# LMP9100_breakout_V2.net
KiCad netlist of a schematic drawn in EAGLE
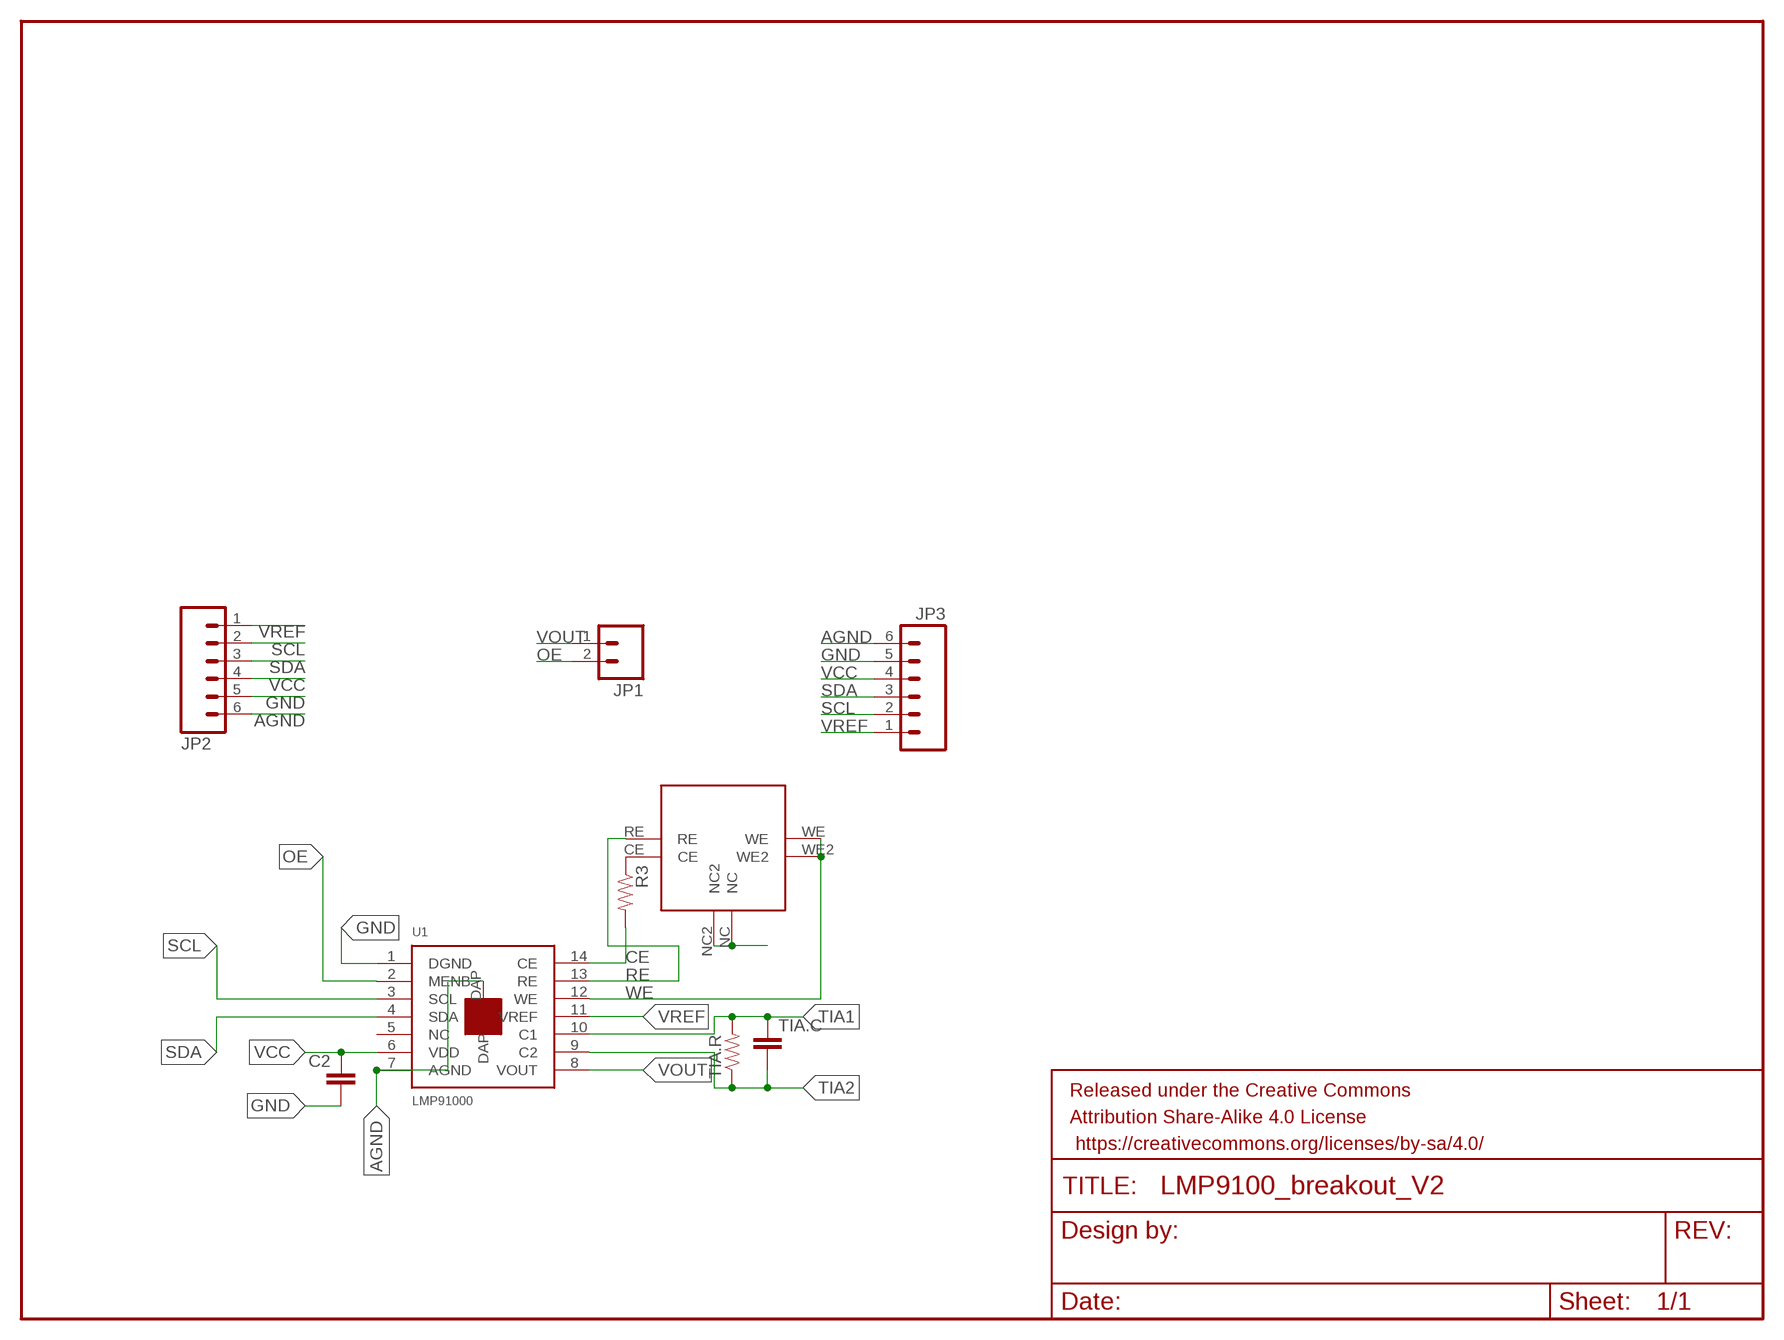
[diagram p0: schematic, sheet 1]

(export (version "E")
  (design (tool "Eeschema 10.0.6"))
  (components
    (comp (ref "C2")
      (value "CAP0603-CAP")
      (footprint "eagle-import:0603-CAP")
      (libsource (lib "eagle-import") (part "CAP0603-CAP"))
    )
    (comp (ref "FRAME1")
      (value "FRAME-LETTER")
      (footprint "eagle-import:CREATIVE_COMMONS")
      (libsource (lib "eagle-import") (part "FRAME-LETTER"))
    )
    (comp (ref "JP1")
      (value "M02PTH")
      (footprint "eagle-import:1X02")
      (libsource (lib "eagle-import") (part "M02PTH"))
    )
    (comp (ref "JP2")
      (value "M06SILK_FEMALE_PTH")
      (footprint "eagle-import:1X06")
      (libsource (lib "eagle-import") (part "M06SILK_FEMALE_PTH"))
    )
    (comp (ref "JP3")
      (value "M06SILK_FEMALE_PTH")
      (footprint "eagle-import:1X06")
      (libsource (lib "eagle-import") (part "M06SILK_FEMALE_PTH"))
    )
    (comp (ref "R3")
      (value "RESISTOR0603-RES")
      (footprint "eagle-import:0603-RES")
      (libsource (lib "eagle-import") (part "RESISTOR0603-RES"))
    )
    (comp (ref "TIA.C")
      (value "CAP0603-CAP")
      (footprint "eagle-import:0603-CAP")
      (libsource (lib "eagle-import") (part "CAP0603-CAP"))
    )
    (comp (ref "TIA.R")
      (value "RESISTOR0603-RES")
      (footprint "eagle-import:0603-RES")
      (libsource (lib "eagle-import") (part "RESISTOR0603-RES"))
    )
    (comp (ref "U$1")
      (value "SPEC-SENSOR")
      (footprint "eagle-import:SPEC-SENSOR")
      (libsource (lib "eagle-import") (part "SPEC-SENSOR"))
    )
    (comp (ref "U1")
      (value "LMP91000")
      (footprint "eagle-import:LMP91000")
      (libsource (lib "eagle-import") (part "LMP91000"))
    )
  )
  (nets
    (net (code "1") (name "/CE") (class "Default")
      (node (ref "R3") (pin "2") (pinfunction "2_2") (pintype "passive"))
      (node (ref "U1") (pin "14") (pinfunction "CE_14") (pintype "bidirectional"))
    )
    (net (code "2") (name "/RE") (class "Default")
      (node (ref "U$1") (pin "RE") (pinfunction "RE_RE") (pintype "bidirectional"))
      (node (ref "U1") (pin "13") (pinfunction "RE_13") (pintype "bidirectional"))
    )
    (net (code "3") (name "/WE") (class "Default")
      (node (ref "U$1") (pin "WE") (pinfunction "WE_WE") (pintype "bidirectional"))
      (node (ref "U$1") (pin "WE2") (pinfunction "WE2_WE2") (pintype "bidirectional"))
      (node (ref "U1") (pin "12") (pinfunction "WE_12") (pintype "bidirectional"))
    )
    (net (code "4") (name "AGND") (class "Default")
      (node (ref "JP2") (pin "6") (pinfunction "6_6") (pintype "passive"))
      (node (ref "JP3") (pin "6") (pinfunction "6_6") (pintype "passive"))
      (node (ref "U1") (pin "7") (pinfunction "AGND_7") (pintype "bidirectional"))
      (node (ref "U1") (pin "DAP") (pinfunction "DAP_DAP") (pintype "bidirectional"))
    )
    (net (code "5") (name "GND") (class "Default")
      (node (ref "C2") (pin "2") (pinfunction "2_2") (pintype "passive"))
      (node (ref "JP2") (pin "5") (pinfunction "5_5") (pintype "passive"))
      (node (ref "JP3") (pin "5") (pinfunction "5_5") (pintype "passive"))
      (node (ref "U$1") (pin "NC") (pinfunction "NC_NC") (pintype "bidirectional"))
      (node (ref "U$1") (pin "NC2") (pinfunction "NC2_NC2") (pintype "bidirectional"))
      (node (ref "U1") (pin "1") (pinfunction "DGND_1") (pintype "bidirectional"))
    )
    (net (code "6") (name "Net-(R3-Pad1)") (class "Default")
      (node (ref "R3") (pin "1") (pinfunction "1_1") (pintype "passive"))
      (node (ref "U$1") (pin "CE") (pinfunction "CE_CE") (pintype "bidirectional"))
    )
    (net (code "7") (name "OE") (class "Default")
      (node (ref "JP1") (pin "2") (pinfunction "2_2") (pintype "passive"))
      (node (ref "U1") (pin "2") (pinfunction "MENB_2") (pintype "bidirectional"))
    )
    (net (code "8") (name "SCL") (class "Default")
      (node (ref "JP2") (pin "2") (pinfunction "2_2") (pintype "passive"))
      (node (ref "JP3") (pin "2") (pinfunction "2_2") (pintype "passive"))
      (node (ref "U1") (pin "3") (pinfunction "SCL_3") (pintype "bidirectional"))
    )
    (net (code "9") (name "SDA") (class "Default")
      (node (ref "JP2") (pin "3") (pinfunction "3_3") (pintype "passive"))
      (node (ref "JP3") (pin "3") (pinfunction "3_3") (pintype "passive"))
      (node (ref "U1") (pin "4") (pinfunction "SDA_4") (pintype "bidirectional"))
    )
    (net (code "10") (name "TIA1") (class "Default")
      (node (ref "TIA.C") (pin "1") (pinfunction "1_1") (pintype "passive"))
      (node (ref "TIA.R") (pin "2") (pinfunction "2_2") (pintype "passive"))
      (node (ref "U1") (pin "10") (pinfunction "C1_10") (pintype "bidirectional"))
    )
    (net (code "11") (name "TIA2") (class "Default")
      (node (ref "TIA.C") (pin "2") (pinfunction "2_2") (pintype "passive"))
      (node (ref "TIA.R") (pin "1") (pinfunction "1_1") (pintype "passive"))
      (node (ref "U1") (pin "9") (pinfunction "C2_9") (pintype "bidirectional"))
    )
    (net (code "12") (name "VCC") (class "Default")
      (node (ref "C2") (pin "1") (pinfunction "1_1") (pintype "passive"))
      (node (ref "JP2") (pin "4") (pinfunction "4_4") (pintype "passive"))
      (node (ref "JP3") (pin "4") (pinfunction "4_4") (pintype "passive"))
      (node (ref "U1") (pin "6") (pinfunction "VDD_6") (pintype "bidirectional"))
    )
    (net (code "13") (name "VOUT") (class "Default")
      (node (ref "JP1") (pin "1") (pinfunction "1_1") (pintype "passive"))
      (node (ref "U1") (pin "8") (pinfunction "VOUT_8") (pintype "bidirectional"))
    )
    (net (code "14") (name "VREF") (class "Default")
      (node (ref "JP2") (pin "1") (pinfunction "1_1") (pintype "passive"))
      (node (ref "JP3") (pin "1") (pinfunction "1_1") (pintype "passive"))
      (node (ref "U1") (pin "11") (pinfunction "VREF_11") (pintype "bidirectional"))
    )
    (net (code "15") (name "unconnected-(U1-NC-Pad5)") (class "Default")
      (node (ref "U1") (pin "5") (pinfunction "NC_5") (pintype "bidirectional"))
    )
  )
)
